# RS485_main.net
KiCad netlist of a schematic drawn in Altium Designer
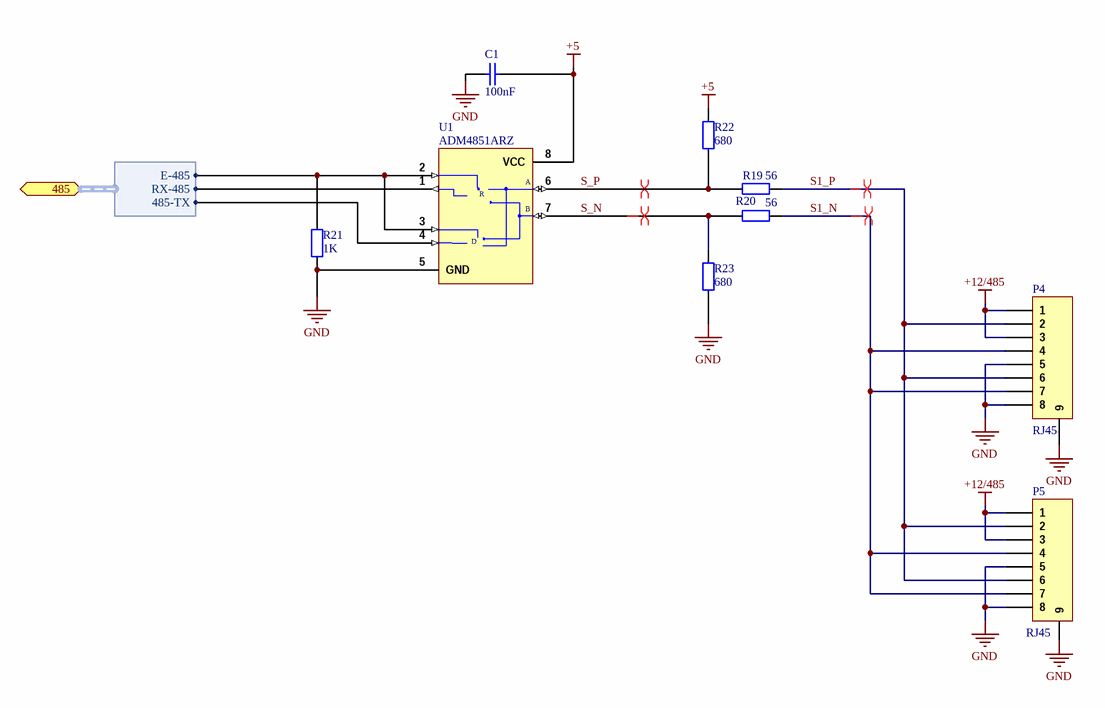
[diagram p0: RS485 main.SchDoc]

(export (version "E")
  (design (tool "Eeschema 10.0.6"))
  (components
    (comp (ref "C1")
      (value "100nF")
      (footprint "C0805")
      (description "Capacitor")
      (fields
        (field (name "MANUFACTURER") "MULTICOMP")
        (field (name "MANUFACTURER PART NUMBER") "MCCA000296")
      )
      (libsource (lib "BRA") (part "Cap 0805 100nF"))
    )
    (comp (ref "P4")
      (value "RJ45")
      (footprint "MOLEX-RJ45_855135013")
      (description "Header, 8-Pin")
      (fields
        (field (name "MANUFACTURER") "MOLEX")
        (field (name "MANUFACTURER PART NUMBER") "85513-5013")
        (field (name "APPROVAL CATEGORY") "UL 94V-0")
        (field (name "LONGUEUR/HAUTEUR") "13")
      )
      (libsource (lib "MAIN BOARD CERES") (part "Header 8"))
    )
    (comp (ref "P5")
      (value "RJ45")
      (footprint "MOLEX-RJ45_855135013")
      (description "Header, 8-Pin")
      (fields
        (field (name "MANUFACTURER") "MOLEX")
        (field (name "MANUFACTURER PART NUMBER") "85513-5013")
        (field (name "APPROVAL CATEGORY") "UL 94V-0")
        (field (name "LONGUEUR/HAUTEUR") "13")
      )
      (libsource (lib "MAIN BOARD CERES") (part "Header 8"))
    )
    (comp (ref "R19")
      (value "56")
      (footprint "R0805")
      (description "Resistor")
      (fields
        (field (name "MANUFACTURER") "MULTICOMP")
        (field (name "MANUFACTURER PART NUMBER") "MC01W0805156R")
      )
      (libsource (lib "BRA") (part "Resistor 0805 56"))
    )
    (comp (ref "R20")
      (value "56")
      (footprint "R0805")
      (description "Resistor")
      (fields
        (field (name "MANUFACTURER") "MULTICOMP")
        (field (name "MANUFACTURER PART NUMBER") "MC01W0805156R")
      )
      (libsource (lib "BRA") (part "Resistor 0805 56"))
    )
    (comp (ref "R21")
      (value "1K")
      (footprint "R0805")
      (description "Resistor")
      (fields
        (field (name "MANUFACTURER") "MULTICOMP")
        (field (name "MANUFACTURER PART NUMBER") "MC0.1W08051%1KFR")
      )
      (libsource (lib "BRA") (part "Resistor 0805 1K"))
    )
    (comp (ref "R22")
      (value "680")
      (footprint "R0805")
      (description "Resistor")
      (fields
        (field (name "MANUFACTURER") "MULTICOMP")
        (field (name "MANUFACTURER PART NUMBER") "MC01W08051680R")
      )
      (libsource (lib "BRA") (part "Resistor 0805 680"))
    )
    (comp (ref "R23")
      (value "680")
      (footprint "R0805")
      (description "Resistor")
      (fields
        (field (name "MANUFACTURER") "MULTICOMP")
        (field (name "MANUFACTURER PART NUMBER") "MC01W08051680R")
      )
      (libsource (lib "BRA") (part "Resistor 0805 680"))
    )
    (comp (ref "U1")
      (value "ADM4851ARZ")
      (footprint "SOIC8")
      (description "Low-Power, Slew-Rate-Limited RS-485/RS-422 Transceiver")
      (fields (field (name "MANUFACTURER") "ANALOG DEVICES"))
      (libsource (lib "Maxim Communication Transceiver") (part "MAX485ESA"))
    )
  )
  (nets
    (net (code "2") (name "+5") (class "Default")
      (node (ref "C1") (pin "1") (pinfunction "1_1") (pintype "passive"))
      (node (ref "R22") (pin "2") (pinfunction "2_2") (pintype "passive"))
      (node (ref "U1") (pin "8") (pinfunction "VCC_8") (pintype "power_in"))
    )
    (net (code "3") (name "+12{slash}485") (class "Default")
      (node (ref "P4") (pin "1") (pinfunction "1_1") (pintype "passive"))
      (node (ref "P4") (pin "3") (pinfunction "3_3") (pintype "passive"))
      (node (ref "P5") (pin "1") (pinfunction "1_1") (pintype "passive"))
      (node (ref "P5") (pin "3") (pinfunction "3_3") (pintype "passive"))
    )
    (net (code "4") (name "/485-TX") (class "Default")
      (node (ref "U1") (pin "4") (pinfunction "DI_4") (pintype "input"))
    )
    (net (code "5") (name "/E-485") (class "Default")
      (node (ref "R21") (pin "2") (pinfunction "2_2") (pintype "passive"))
      (node (ref "U1") (pin "2") (pinfunction "~{RE}_2") (pintype "input"))
      (node (ref "U1") (pin "3") (pinfunction "DE_3") (pintype "input"))
    )
    (net (code "6") (name "/RX-485") (class "Default")
      (node (ref "U1") (pin "1") (pinfunction "RO_1") (pintype "output"))
    )
    (net (code "7") (name "/S1_N") (class "Default")
      (node (ref "P4") (pin "4") (pinfunction "4_4") (pintype "passive"))
      (node (ref "P4") (pin "7") (pinfunction "7_7") (pintype "passive"))
      (node (ref "P5") (pin "4") (pinfunction "4_4") (pintype "passive"))
      (node (ref "P5") (pin "7") (pinfunction "7_7") (pintype "passive"))
      (node (ref "R20") (pin "2") (pinfunction "2_2") (pintype "passive"))
    )
    (net (code "8") (name "/S1_P") (class "Default")
      (node (ref "P4") (pin "2") (pinfunction "2_2") (pintype "passive"))
      (node (ref "P4") (pin "6") (pinfunction "6_6") (pintype "passive"))
      (node (ref "P5") (pin "2") (pinfunction "2_2") (pintype "passive"))
      (node (ref "P5") (pin "6") (pinfunction "6_6") (pintype "passive"))
      (node (ref "R19") (pin "2") (pinfunction "2_2") (pintype "passive"))
    )
    (net (code "9") (name "/S_N") (class "Default")
      (node (ref "R20") (pin "1") (pinfunction "1_1") (pintype "passive"))
      (node (ref "R23") (pin "2") (pinfunction "2_2") (pintype "passive"))
      (node (ref "U1") (pin "7") (pinfunction "B_7") (pintype "bidirectional"))
    )
    (net (code "10") (name "/S_P") (class "Default")
      (node (ref "R19") (pin "1") (pinfunction "1_1") (pintype "passive"))
      (node (ref "R22") (pin "1") (pinfunction "1_1") (pintype "passive"))
      (node (ref "U1") (pin "6") (pinfunction "A_6") (pintype "bidirectional"))
    )
    (net (code "12") (name "GND") (class "Default")
      (node (ref "C1") (pin "2") (pinfunction "2_2") (pintype "passive"))
      (node (ref "P4") (pin "5") (pinfunction "5_5") (pintype "passive"))
      (node (ref "P4") (pin "8") (pinfunction "8_8") (pintype "passive"))
      (node (ref "P4") (pin "9") (pinfunction "9_9") (pintype "passive"))
      (node (ref "P5") (pin "5") (pinfunction "5_5") (pintype "passive"))
      (node (ref "P5") (pin "8") (pinfunction "8_8") (pintype "passive"))
      (node (ref "R21") (pin "1") (pinfunction "1_1") (pintype "passive"))
      (node (ref "R23") (pin "1") (pinfunction "1_1") (pintype "passive"))
      (node (ref "U1") (pin "5") (pinfunction "GND_5") (pintype "power_in"))
    )
    (net (code "13") (name "unconnected-(P5-Pad9)") (class "Default")
      (node (ref "P5") (pin "9") (pinfunction "9_9") (pintype "passive"))
    )
  )
)
